# IMU.net
KiCad netlist of a schematic drawn in Altium Designer
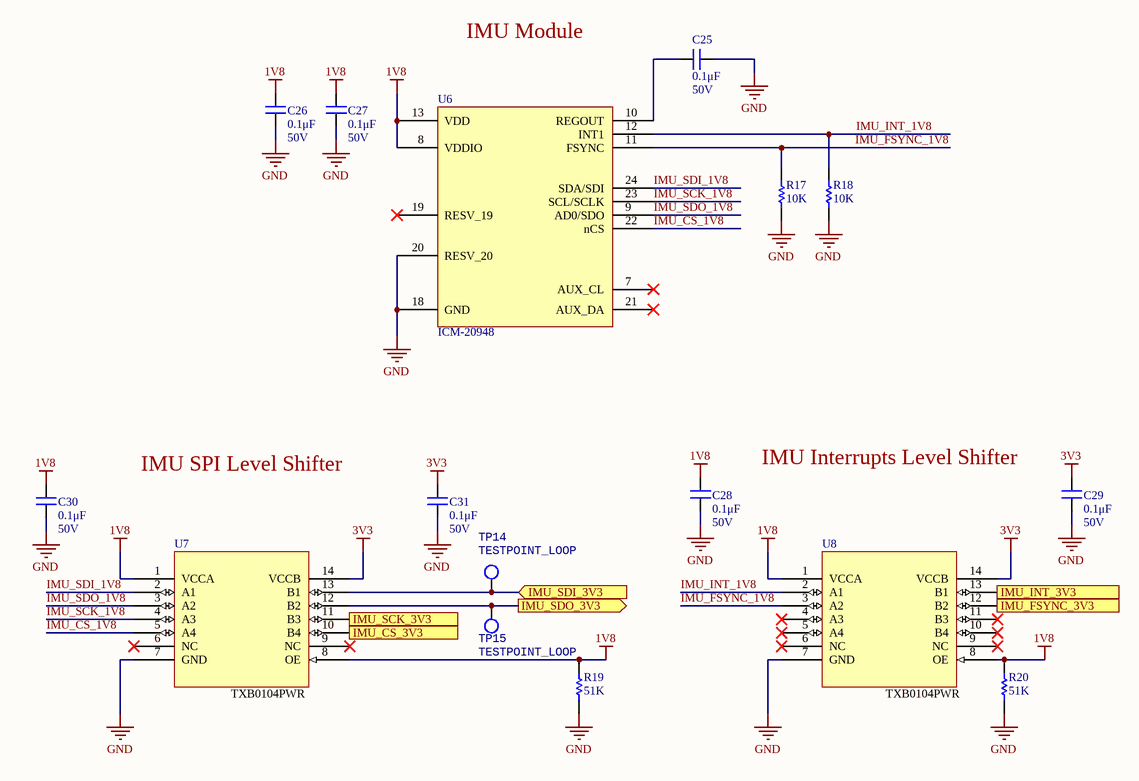
[diagram p0: IMU.SchDoc]

(export (version "E")
  (design (tool "Eeschema 10.0.6"))
  (components
    (comp (ref "C25")
      (value "0.1μF")
      (footprint "CAP2012")
      (description "CAP CER 0.1UF 50V X7R 0805")
      (fields
        (field (name "TOLERANCE") "10%")
        (field (name "VOLTAGE RATING") "50V")
        (field (name "Comment") "CAP_0.1uF_50V_0805")
      )
      (libsource (lib "UWRT_Schematic_Library_2020") (part "CAP_0.1uF_50V_0805"))
    )
    (comp (ref "C26")
      (value "0.1μF")
      (footprint "CAP2012")
      (description "CAP CER 0.1UF 50V X7R 0805")
      (fields
        (field (name "TOLERANCE") "10%")
        (field (name "VOLTAGE RATING") "50V")
        (field (name "Comment") "CAP_0.1uF_50V_0805")
      )
      (libsource (lib "UWRT_Schematic_Library_2020") (part "CAP_0.1uF_50V_0805"))
    )
    (comp (ref "C27")
      (value "0.1μF")
      (footprint "CAP2012")
      (description "CAP CER 0.1UF 50V X7R 0805")
      (fields
        (field (name "TOLERANCE") "10%")
        (field (name "VOLTAGE RATING") "50V")
        (field (name "Comment") "CAP_0.1uF_50V_0805")
      )
      (libsource (lib "UWRT_Schematic_Library_2020") (part "CAP_0.1uF_50V_0805"))
    )
    (comp (ref "C28")
      (value "0.1μF")
      (footprint "CAP2012")
      (description "CAP CER 0.1UF 50V X7R 0805")
      (fields
        (field (name "TOLERANCE") "10%")
        (field (name "VOLTAGE RATING") "50V")
        (field (name "Comment") "CAP_0.1uF_50V_0805")
      )
      (libsource (lib "UWRT_Schematic_Library_2020") (part "CAP_0.1uF_50V_0805"))
    )
    (comp (ref "C29")
      (value "0.1μF")
      (footprint "CAP2012")
      (description "CAP CER 0.1UF 50V X7R 0805")
      (fields
        (field (name "TOLERANCE") "10%")
        (field (name "VOLTAGE RATING") "50V")
        (field (name "Comment") "CAP_0.1uF_50V_0805")
      )
      (libsource (lib "UWRT_Schematic_Library_2020") (part "CAP_0.1uF_50V_0805"))
    )
    (comp (ref "C30")
      (value "0.1μF")
      (footprint "CAP2012")
      (description "CAP CER 0.1UF 50V X7R 0805")
      (fields
        (field (name "TOLERANCE") "10%")
        (field (name "VOLTAGE RATING") "50V")
        (field (name "Comment") "CAP_0.1uF_50V_0805")
      )
      (libsource (lib "UWRT_Schematic_Library_2020") (part "CAP_0.1uF_50V_0805"))
    )
    (comp (ref "C31")
      (value "0.1μF")
      (footprint "CAP2012")
      (description "CAP CER 0.1UF 50V X7R 0805")
      (fields
        (field (name "TOLERANCE") "10%")
        (field (name "VOLTAGE RATING") "50V")
        (field (name "Comment") "CAP_0.1uF_50V_0805")
      )
      (libsource (lib "UWRT_Schematic_Library_2020") (part "CAP_0.1uF_50V_0805"))
    )
    (comp (ref "R17")
      (value "10K")
      (footprint "RESC0603(1608)_N")
      (description "RES SMD 10K OHM 5% 1/10W 0603")
      (fields (field (name "TOLERANCE") "5%") (field (name "Comment") "RES_10K_0603"))
      (libsource (lib "UWRT_Schematic_Library_2020") (part "RES_10K_0603"))
    )
    (comp (ref "R18")
      (value "10K")
      (footprint "RESC0603(1608)_N")
      (description "RES SMD 10K OHM 5% 1/10W 0603")
      (fields (field (name "TOLERANCE") "5%") (field (name "Comment") "RES_10K_0603"))
      (libsource (lib "UWRT_Schematic_Library_2020") (part "RES_10K_0603"))
    )
    (comp (ref "R19")
      (value "51K")
      (footprint "RESC1608X55N")
      (description "RES SMD 51K OHM 5% 1/10W 0603")
      (fields (field (name "TOLERANCE") "5%") (field (name "Comment") "RES_51K_0603"))
      (libsource (lib "UWRT_Schematic_Library_2020") (part "RES_51K_0603"))
    )
    (comp (ref "R20")
      (value "51K")
      (footprint "RESC1608X55N")
      (description "RES SMD 51K OHM 5% 1/10W 0603")
      (fields (field (name "TOLERANCE") "5%") (field (name "Comment") "RES_51K_0603"))
      (libsource (lib "UWRT_Schematic_Library_2020") (part "RES_51K_0603"))
    )
    (comp (ref "TP14")
      (value "TESTPOINT_LOOP")
      (footprint "TESTPOINT_LOOP")
      (description "PC TEST POINT MINIATURE WHITE")
      (libsource (lib "UWRT_Schematic_Library_2020") (part "TESTPOINT_LOOP"))
    )
    (comp (ref "TP15")
      (value "TESTPOINT_LOOP")
      (footprint "TESTPOINT_LOOP")
      (description "PC TEST POINT MINIATURE WHITE")
      (libsource (lib "UWRT_Schematic_Library_2020") (part "TESTPOINT_LOOP"))
    )
    (comp (ref "U6")
      (value "IC_9DOF_IMU")
      (footprint "ICM-20948")
      (description "IMU ACCEL/GYRO/COMPI2C/SPI 24QFN")
      (fields
        (field (name "MANUFACTURER") "TDK InvenSense")
        (field (name "MANUFACTURER PART NUMBER") "ICM-20948")
      )
      (libsource (lib "UWRT_Schematic_Library_2020") (part "IC_9DOF_IMU"))
    )
    (comp (ref "U7")
      (value "TXB0104PWR")
      (footprint "UWRT_Footprint_Library_2020:PW14")
      (fields
        (field (name "GENERIC_PART_NUMBER") "TXB0104")
        (field (name "MANUFACTURER PART NUMBER 1") "TXB0104PWR")
      )
      (libsource (lib "UWRT_Schematic_Library_2020") (part "IC_4CH_LVL_SHIFTER"))
    )
    (comp (ref "U8")
      (value "TXB0104PWR")
      (footprint "UWRT_Footprint_Library_2020:PW14")
      (fields
        (field (name "GENERIC_PART_NUMBER") "TXB0104")
        (field (name "MANUFACTURER PART NUMBER 1") "TXB0104PWR")
      )
      (libsource (lib "UWRT_Schematic_Library_2020") (part "IC_4CH_LVL_SHIFTER"))
    )
  )
  (nets
    (net (code "1") (name "/IMU_CS_1V8") (class "Default")
      (node (ref "U6") (pin "22") (pinfunction "nCS_22") (pintype "passive"))
      (node (ref "U7") (pin "5") (pinfunction "A4_5") (pintype "bidirectional"))
    )
    (net (code "2") (name "/IMU_CS_3V3") (class "Default")
      (node (ref "U7") (pin "10") (pinfunction "B4_10") (pintype "bidirectional"))
    )
    (net (code "3") (name "/IMU_FSYNC_1V8") (class "Default")
      (node (ref "R17") (pin "2") (pinfunction "2_2") (pintype "passive"))
      (node (ref "U6") (pin "11") (pinfunction "FSYNC_11") (pintype "passive"))
      (node (ref "U8") (pin "3") (pinfunction "A2_3") (pintype "bidirectional"))
    )
    (net (code "4") (name "/IMU_FSYNC_3V3") (class "Default")
      (node (ref "U8") (pin "12") (pinfunction "B2_12") (pintype "bidirectional"))
    )
    (net (code "5") (name "/IMU_INT_1V8") (class "Default")
      (node (ref "R18") (pin "2") (pinfunction "2_2") (pintype "passive"))
      (node (ref "U6") (pin "12") (pinfunction "INT1_12") (pintype "passive"))
      (node (ref "U8") (pin "2") (pinfunction "A1_2") (pintype "bidirectional"))
    )
    (net (code "6") (name "/IMU_INT_3V3") (class "Default")
      (node (ref "U8") (pin "13") (pinfunction "B1_13") (pintype "bidirectional"))
    )
    (net (code "7") (name "/IMU_SCK_1V8") (class "Default")
      (node (ref "U6") (pin "23") (pinfunction "SCL/SCLK_23") (pintype "passive"))
      (node (ref "U7") (pin "4") (pinfunction "A3_4") (pintype "bidirectional"))
    )
    (net (code "8") (name "/IMU_SCK_3V3") (class "Default")
      (node (ref "U7") (pin "11") (pinfunction "B3_11") (pintype "bidirectional"))
    )
    (net (code "9") (name "/IMU_SDI_1V8") (class "Default")
      (node (ref "U6") (pin "24") (pinfunction "SDA/SDI_24") (pintype "passive"))
      (node (ref "U7") (pin "2") (pinfunction "A1_2") (pintype "bidirectional"))
    )
    (net (code "10") (name "/IMU_SDI_3V3") (class "Default")
      (node (ref "TP14") (pin "1") (pintype "passive"))
      (node (ref "U7") (pin "13") (pinfunction "B1_13") (pintype "bidirectional"))
    )
    (net (code "11") (name "/IMU_SDO_1V8") (class "Default")
      (node (ref "U6") (pin "9") (pinfunction "AD0/SDO_9") (pintype "passive"))
      (node (ref "U7") (pin "3") (pinfunction "A2_3") (pintype "bidirectional"))
    )
    (net (code "12") (name "/IMU_SDO_3V3") (class "Default")
      (node (ref "TP15") (pin "1") (pintype "passive"))
      (node (ref "U7") (pin "12") (pinfunction "B2_12") (pintype "bidirectional"))
    )
    (net (code "13") (name "1V8") (class "Default")
      (node (ref "C26") (pin "2") (pinfunction "2_2") (pintype "passive"))
      (node (ref "C27") (pin "2") (pinfunction "2_2") (pintype "passive"))
      (node (ref "C28") (pin "2") (pinfunction "2_2") (pintype "passive"))
      (node (ref "C30") (pin "2") (pinfunction "2_2") (pintype "passive"))
      (node (ref "R19") (pin "2") (pinfunction "2_2") (pintype "passive"))
      (node (ref "R20") (pin "2") (pinfunction "2_2") (pintype "passive"))
      (node (ref "U6") (pin "13") (pinfunction "VDD_13") (pintype "passive"))
      (node (ref "U6") (pin "8") (pinfunction "VDDIO_8") (pintype "passive"))
      (node (ref "U7") (pin "1") (pinfunction "VCCA_1") (pintype "power_in"))
      (node (ref "U7") (pin "8") (pinfunction "OE_8") (pintype "input"))
      (node (ref "U8") (pin "1") (pinfunction "VCCA_1") (pintype "power_in"))
      (node (ref "U8") (pin "8") (pinfunction "OE_8") (pintype "input"))
    )
    (net (code "14") (name "3V3") (class "Default")
      (node (ref "C29") (pin "2") (pinfunction "2_2") (pintype "passive"))
      (node (ref "C31") (pin "2") (pinfunction "2_2") (pintype "passive"))
      (node (ref "U7") (pin "14") (pinfunction "VCCB_14") (pintype "power_in"))
      (node (ref "U8") (pin "14") (pinfunction "VCCB_14") (pintype "power_in"))
    )
    (net (code "15") (name "GND") (class "Default")
      (node (ref "C25") (pin "2") (pinfunction "2_2") (pintype "passive"))
      (node (ref "C26") (pin "1") (pinfunction "1_1") (pintype "passive"))
      (node (ref "C27") (pin "1") (pinfunction "1_1") (pintype "passive"))
      (node (ref "C28") (pin "1") (pinfunction "1_1") (pintype "passive"))
      (node (ref "C29") (pin "1") (pinfunction "1_1") (pintype "passive"))
      (node (ref "C30") (pin "1") (pinfunction "1_1") (pintype "passive"))
      (node (ref "C31") (pin "1") (pinfunction "1_1") (pintype "passive"))
      (node (ref "R17") (pin "1") (pinfunction "1_1") (pintype "passive"))
      (node (ref "R18") (pin "1") (pinfunction "1_1") (pintype "passive"))
      (node (ref "R19") (pin "1") (pinfunction "1_1") (pintype "passive"))
      (node (ref "R20") (pin "1") (pinfunction "1_1") (pintype "passive"))
      (node (ref "U6") (pin "18") (pinfunction "GND_18") (pintype "passive"))
      (node (ref "U6") (pin "20") (pinfunction "RESV_20_20") (pintype "passive"))
      (node (ref "U7") (pin "7") (pinfunction "GND_7") (pintype "power_in"))
      (node (ref "U8") (pin "7") (pinfunction "GND_7") (pintype "power_in"))
    )
    (net (code "16") (name "Net-(U6-REGOUT)") (class "Default")
      (node (ref "C25") (pin "1") (pinfunction "1_1") (pintype "passive"))
      (node (ref "U6") (pin "10") (pinfunction "REGOUT_10") (pintype "passive"))
    )
    (net (code "17") (name "unconnected-(U6-AUX_CL-Pad7)") (class "Default")
      (node (ref "U6") (pin "7") (pinfunction "AUX_CL_7") (pintype "passive+no_connect"))
    )
    (net (code "18") (name "unconnected-(U6-AUX_DA-Pad21)") (class "Default")
      (node (ref "U6") (pin "21") (pinfunction "AUX_DA_21") (pintype "passive+no_connect"))
    )
    (net (code "19") (name "unconnected-(U6-RESV_19-Pad19)") (class "Default")
      (node (ref "U6") (pin "19") (pinfunction "RESV_19_19") (pintype "passive+no_connect"))
    )
    (net (code "20") (name "unconnected-(U7-NC-Pad6)") (class "Default")
      (node (ref "U7") (pin "6") (pinfunction "NC_6") (pintype "passive+no_connect"))
    )
    (net (code "21") (name "unconnected-(U7-NC-Pad9)") (class "Default")
      (node (ref "U7") (pin "9") (pinfunction "NC_9") (pintype "passive+no_connect"))
    )
    (net (code "22") (name "unconnected-(U8-A3-Pad4)") (class "Default")
      (node (ref "U8") (pin "4") (pinfunction "A3_4") (pintype "bidirectional+no_connect"))
    )
    (net (code "23") (name "unconnected-(U8-A4-Pad5)") (class "Default")
      (node (ref "U8") (pin "5") (pinfunction "A4_5") (pintype "bidirectional+no_connect"))
    )
    (net (code "24") (name "unconnected-(U8-B3-Pad11)") (class "Default")
      (node (ref "U8") (pin "11") (pinfunction "B3_11") (pintype "bidirectional+no_connect"))
    )
    (net (code "25") (name "unconnected-(U8-B4-Pad10)") (class "Default")
      (node (ref "U8") (pin "10") (pinfunction "B4_10") (pintype "bidirectional+no_connect"))
    )
    (net (code "26") (name "unconnected-(U8-NC-Pad6)") (class "Default")
      (node (ref "U8") (pin "6") (pinfunction "NC_6") (pintype "passive+no_connect"))
    )
    (net (code "27") (name "unconnected-(U8-NC-Pad9)") (class "Default")
      (node (ref "U8") (pin "9") (pinfunction "NC_9") (pintype "passive+no_connect"))
    )
  )
)
